# NE-CurrentSense-V1_0.net
KiCad netlist of a schematic drawn in Altium Designer
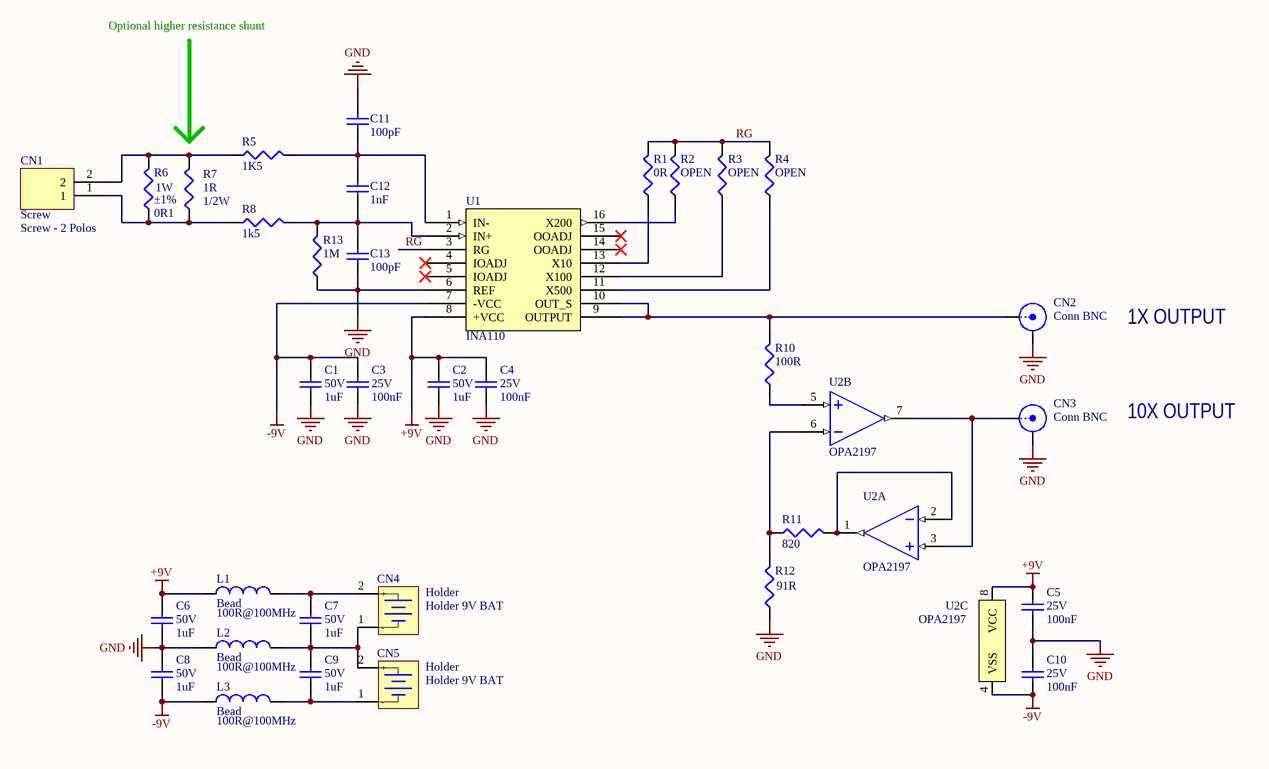
[diagram p0: NE-CurrentSense-V1.0.SchDoc]

(export (version "E")
  (design (tool "Eeschema 10.0.6"))
  (components
    (comp (ref "C1")
      (value "1uF")
      (footprint "CC0603")
      (description "Capacitor (Semiconductor SIM Model)")
      (fields (field (name "TENSÃO") "50V") (field (name "Comment") "Capacitor Cerâmico"))
      (libsource (lib "NavarroCAP") (part "Cap 1uF 50V 0603 X5R"))
    )
    (comp (ref "C2")
      (value "1uF")
      (footprint "CC0603")
      (description "Capacitor (Semiconductor SIM Model)")
      (fields (field (name "TENSÃO") "50V") (field (name "Comment") "Capacitor Cerâmico"))
      (libsource (lib "NavarroCAP") (part "Cap 1uF 50V 0603 X5R"))
    )
    (comp (ref "C3")
      (value "100nF")
      (footprint "CC0603")
      (description "Capacitor (Semiconductor SIM Model)")
      (fields (field (name "TENSÃO") "25V") (field (name "Comment") "Capacitor Cerâmico"))
      (libsource (lib "NavarroCAP") (part "Cap 100nF 25V 0603 X7R"))
    )
    (comp (ref "C4")
      (value "100nF")
      (footprint "CC0603")
      (description "Capacitor (Semiconductor SIM Model)")
      (fields (field (name "TENSÃO") "25V") (field (name "Comment") "Capacitor Cerâmico"))
      (libsource (lib "NavarroCAP") (part "Cap 100nF 25V 0603 X7R"))
    )
    (comp (ref "C5")
      (value "100nF")
      (footprint "CC0603")
      (description "Capacitor (Semiconductor SIM Model)")
      (fields (field (name "TENSÃO") "25V") (field (name "Comment") "Capacitor Cerâmico"))
      (libsource (lib "NavarroCAP") (part "Cap 100nF 25V 0603 X7R"))
    )
    (comp (ref "C6")
      (value "1uF")
      (footprint "CC0603")
      (description "Capacitor (Semiconductor SIM Model)")
      (fields (field (name "TENSÃO") "50V") (field (name "Comment") "Capacitor Cerâmico"))
      (libsource (lib "NavarroCAP") (part "Cap 1uF 50V 0603 X5R"))
    )
    (comp (ref "C7")
      (value "1uF")
      (footprint "CC0603")
      (description "Capacitor (Semiconductor SIM Model)")
      (fields (field (name "TENSÃO") "50V") (field (name "Comment") "Capacitor Cerâmico"))
      (libsource (lib "NavarroCAP") (part "Cap 1uF 50V 0603 X5R"))
    )
    (comp (ref "C8")
      (value "1uF")
      (footprint "CC0603")
      (description "Capacitor (Semiconductor SIM Model)")
      (fields (field (name "TENSÃO") "50V") (field (name "Comment") "Capacitor Cerâmico"))
      (libsource (lib "NavarroCAP") (part "Cap 1uF 50V 0603 X5R"))
    )
    (comp (ref "C9")
      (value "1uF")
      (footprint "CC0603")
      (description "Capacitor (Semiconductor SIM Model)")
      (fields (field (name "TENSÃO") "50V") (field (name "Comment") "Capacitor Cerâmico"))
      (libsource (lib "NavarroCAP") (part "Cap 1uF 50V 0603 X5R"))
    )
    (comp (ref "C10")
      (value "100nF")
      (footprint "CC0603")
      (description "Capacitor (Semiconductor SIM Model)")
      (fields (field (name "TENSÃO") "25V") (field (name "Comment") "Capacitor Cerâmico"))
      (libsource (lib "NavarroCAP") (part "Cap 100nF 25V 0603 X7R"))
    )
    (comp (ref "C11")
      (value "100pF")
      (footprint "CC0603")
      (description "Capacitor (Semiconductor SIM Model)")
      (fields (field (name "Comment") "Capacitor Cerâmico"))
      (libsource (lib "NavarroCAP") (part "Cap OPEN 0603"))
    )
    (comp (ref "C12")
      (value "1nF")
      (footprint "CC0603")
      (description "Capacitor (Semiconductor SIM Model)")
      (fields (field (name "Comment") "Capacitor Cerâmico"))
      (libsource (lib "NavarroCAP") (part "Cap OPEN 0603"))
    )
    (comp (ref "C13")
      (value "100pF")
      (footprint "CC0603")
      (description "Capacitor (Semiconductor SIM Model)")
      (fields (field (name "Comment") "Capacitor Cerâmico"))
      (libsource (lib "NavarroCAP") (part "Cap OPEN 0603"))
    )
    (comp (ref "CN1")
      (value "Screw")
      (footprint "CONN SCREW-2N P5.08")
      (description "Conector Screw Block")
      (fields (field (name "ALTIUM_VALUE") "Screw - 2 Polos"))
      (libsource (lib "TecnocladeCON") (part "Screw-2 300V 12A P5.08mm"))
    )
    (comp (ref "CN2")
      (value "Conn BNC")
      (footprint "CONN BNC-JACK")
      (description "Conector BNC")
      (libsource (lib "TecnocladeCON") (part "Conn BNC"))
    )
    (comp (ref "CN3")
      (value "Conn BNC")
      (footprint "CONN BNC-JACK")
      (description "Conector BNC")
      (libsource (lib "TecnocladeCON") (part "Conn BNC"))
    )
    (comp (ref "CN4")
      (value "Holder")
      (footprint "BATTHOLDER-9V-BH9V-PC-ND")
      (fields (field (name "ALTIUM_VALUE") "Holder 9V BAT"))
      (libsource (lib "NavarroCON") (part "BattHolder 9V"))
    )
    (comp (ref "CN5")
      (value "Holder")
      (footprint "BATTHOLDER-9V-BH9V-PC-ND")
      (fields (field (name "ALTIUM_VALUE") "Holder 9V BAT"))
      (libsource (lib "NavarroCON") (part "BattHolder 9V"))
    )
    (comp (ref "L1")
      (value "Bead")
      (footprint "CC0603")
      (fields (field (name "ALTIUM_VALUE") "100R@100MHz"))
      (libsource (lib "NavarroIND") (part "Bd 100R@100MHz 0603 2A"))
    )
    (comp (ref "L2")
      (value "Bead")
      (footprint "CC0603")
      (fields (field (name "ALTIUM_VALUE") "100R@100MHz"))
      (libsource (lib "NavarroIND") (part "Bd 100R@100MHz 0603 2A"))
    )
    (comp (ref "L3")
      (value "Bead")
      (footprint "CC0603")
      (fields (field (name "ALTIUM_VALUE") "100R@100MHz"))
      (libsource (lib "NavarroIND") (part "Bd 100R@100MHz 0603 2A"))
    )
    (comp (ref "R1")
      (value "0R")
      (footprint "CC0603")
      (description "Resistor")
      (libsource (lib "NavarroRES") (part "Res 0R 0603 1/10W"))
    )
    (comp (ref "R2")
      (value "OPEN")
      (footprint "CC0603")
      (description "Resistor")
      (fields (field (name "Comment") "Resistor Open"))
      (libsource (lib "NavarroRES") (part "Res Open 0603"))
    )
    (comp (ref "R3")
      (value "OPEN")
      (footprint "CC0603")
      (description "Resistor")
      (fields (field (name "Comment") "Resistor Open"))
      (libsource (lib "NavarroRES") (part "Res Open 0603"))
    )
    (comp (ref "R4")
      (value "OPEN")
      (footprint "CC0603")
      (description "Resistor")
      (fields (field (name "Comment") "Resistor Open"))
      (libsource (lib "NavarroRES") (part "Res Open 0603"))
    )
    (comp (ref "R5")
      (value "1K5")
      (footprint "CC0603")
      (description "Resistor")
      (libsource (lib "NavarroRES") (part "Res 0R 0603 1/10W"))
    )
    (comp (ref "R6")
      (value "0R1")
      (footprint "CC2010")
      (description "Resistor Shunt")
      (fields
        (field (name "POTÊNCIA") "1W")
        (field (name "TOLERÂNCIA") "±1%")
        (field (name "Comment") "Resistor")
      )
      (libsource (lib "NavarroRES") (part "Shunt 0R1 1% 2010 1W"))
    )
    (comp (ref "R7")
      (value "1R")
      (footprint "CC1206")
      (description "Resistor")
      (fields (field (name "POTÊNCIA") "1/2W"))
      (libsource (lib "NavarroRES") (part "Res 931R 1% 0603 1/10W"))
    )
    (comp (ref "R8")
      (value "1k5")
      (footprint "CC0603")
      (description "Resistor")
      (libsource (lib "NavarroRES") (part "Res 0R 0603 1/10W"))
    )
    (comp (ref "R10")
      (value "100R")
      (footprint "CC0603")
      (description "Resistor")
      (libsource (lib "NavarroRES") (part "Res 100R 5% 0603 1/10W"))
    )
    (comp (ref "R11")
      (value "820")
      (footprint "CC0603")
      (description "Resistor")
      (libsource (lib "NavarroRES") (part "Res 9K76 1% 0603 1/10W"))
    )
    (comp (ref "R12")
      (value "91R")
      (footprint "CC0603")
      (description "Resistor")
      (libsource (lib "NavarroRES") (part "Res 976R 1% 0603 1/10W"))
    )
    (comp (ref "R13")
      (value "1M")
      (footprint "CC0603")
      (description "Resistor")
      (libsource (lib "NavarroRES") (part "Res 1M 1% 0603 1/10W"))
    )
    (comp (ref "U1")
      (value "INA110")
      (footprint "SOIC-16N_WIDE")
      (description "Fast-Settling FET-Input  INSTRUMENTATION AMPLIFIER")
      (libsource (lib "Navarro") (part "INA110"))
    )
    (comp (ref "U2")
      (value "OPA2197")
      (footprint "SOIC-8N")
      (description "OPAx197 36-V, Precision, Rail-to-Rail Input/Output, Low Offset Voltage, Operational Amplifiers")
      (libsource (lib "Navarro") (part "OPA2197"))
    )
  )
  (nets
    (net (code "1") (name "+9V") (class "Default")
      (node (ref "C2") (pin "2") (pinfunction "2_2") (pintype "passive"))
      (node (ref "C4") (pin "2") (pinfunction "2_2") (pintype "passive"))
      (node (ref "C5") (pin "2") (pinfunction "2_2") (pintype "passive"))
      (node (ref "C6") (pin "2") (pinfunction "2_2") (pintype "passive"))
      (node (ref "L1") (pin "1") (pinfunction "1_1") (pintype "passive"))
      (node (ref "U1") (pin "8") (pinfunction "+VCC_8") (pintype "power_in"))
      (node (ref "U2") (pin "8") (pinfunction "VCC_8") (pintype "power_in"))
    )
    (net (code "2") (name "-9V") (class "Default")
      (node (ref "C1") (pin "2") (pinfunction "2_2") (pintype "passive"))
      (node (ref "C10") (pin "1") (pinfunction "1_1") (pintype "passive"))
      (node (ref "C3") (pin "2") (pinfunction "2_2") (pintype "passive"))
      (node (ref "C8") (pin "1") (pinfunction "1_1") (pintype "passive"))
      (node (ref "L3") (pin "1") (pinfunction "1_1") (pintype "passive"))
      (node (ref "U1") (pin "7") (pinfunction "-VCC_7") (pintype "power_in"))
      (node (ref "U2") (pin "4") (pinfunction "VSS_4") (pintype "power_in"))
    )
    (net (code "3") (name "/RG") (class "Default")
      (node (ref "R1") (pin "2") (pinfunction "2_2") (pintype "passive"))
      (node (ref "R2") (pin "2") (pinfunction "2_2") (pintype "passive"))
      (node (ref "R3") (pin "2") (pinfunction "2_2") (pintype "passive"))
      (node (ref "R4") (pin "2") (pinfunction "2_2") (pintype "passive"))
      (node (ref "U1") (pin "3") (pinfunction "RG_3") (pintype "passive"))
    )
    (net (code "4") (name "GND") (class "Default")
      (node (ref "C1") (pin "1") (pinfunction "1_1") (pintype "passive"))
      (node (ref "C10") (pin "2") (pinfunction "2_2") (pintype "passive"))
      (node (ref "C11") (pin "2") (pinfunction "2_2") (pintype "passive"))
      (node (ref "C13") (pin "1") (pinfunction "1_1") (pintype "passive"))
      (node (ref "C2") (pin "1") (pinfunction "1_1") (pintype "passive"))
      (node (ref "C3") (pin "1") (pinfunction "1_1") (pintype "passive"))
      (node (ref "C4") (pin "1") (pinfunction "1_1") (pintype "passive"))
      (node (ref "C5") (pin "1") (pinfunction "1_1") (pintype "passive"))
      (node (ref "C6") (pin "1") (pinfunction "1_1") (pintype "passive"))
      (node (ref "C8") (pin "2") (pinfunction "2_2") (pintype "passive"))
      (node (ref "CN2") (pin "2") (pinfunction "Y_2") (pintype "passive"))
      (node (ref "CN3") (pin "2") (pinfunction "Y_2") (pintype "passive"))
      (node (ref "L2") (pin "1") (pinfunction "1_1") (pintype "passive"))
      (node (ref "R12") (pin "1") (pinfunction "1_1") (pintype "passive"))
      (node (ref "R13") (pin "1") (pinfunction "1_1") (pintype "passive"))
      (node (ref "U1") (pin "6") (pinfunction "REF_6") (pintype "passive"))
    )
    (net (code "5") (name "Net-(CN1-Pad1)") (class "Default")
      (node (ref "CN1") (pin "1") (pinfunction "1_1") (pintype "passive"))
      (node (ref "R6") (pin "1") (pinfunction "1_1") (pintype "passive"))
      (node (ref "R7") (pin "1") (pinfunction "1_1") (pintype "passive"))
      (node (ref "R8") (pin "1") (pinfunction "1_1") (pintype "passive"))
    )
    (net (code "6") (name "Net-(CN1-Pad2)") (class "Default")
      (node (ref "CN1") (pin "2") (pinfunction "2_2") (pintype "passive"))
      (node (ref "R5") (pin "1") (pinfunction "1_1") (pintype "passive"))
      (node (ref "R6") (pin "2") (pinfunction "2_2") (pintype "passive"))
      (node (ref "R7") (pin "2") (pinfunction "2_2") (pintype "passive"))
    )
    (net (code "7") (name "Net-(CN2-X)") (class "Default")
      (node (ref "CN2") (pin "1") (pinfunction "X_1") (pintype "passive"))
      (node (ref "R10") (pin "2") (pinfunction "2_2") (pintype "passive"))
      (node (ref "U1") (pin "10") (pinfunction "OUT_S_10") (pintype "passive"))
      (node (ref "U1") (pin "9") (pinfunction "OUTPUT_9") (pintype "passive"))
    )
    (net (code "8") (name "Net-(CN3-X)") (class "Default")
      (node (ref "CN3") (pin "1") (pinfunction "X_1") (pintype "passive"))
      (node (ref "U2") (pin "3") (pinfunction "INA+_3") (pintype "input"))
      (node (ref "U2") (pin "7") (pinfunction "OUTB_7") (pintype "output"))
    )
    (net (code "9") (name "Net-(CN4-+)") (class "Default")
      (node (ref "C7") (pin "2") (pinfunction "2_2") (pintype "passive"))
      (node (ref "CN4") (pin "2") (pinfunction "+_2") (pintype "power_in"))
      (node (ref "L1") (pin "2") (pinfunction "2_2") (pintype "passive"))
    )
    (net (code "10") (name "Net-(CN4--)") (class "Default")
      (node (ref "C7") (pin "1") (pinfunction "1_1") (pintype "passive"))
      (node (ref "C9") (pin "2") (pinfunction "2_2") (pintype "passive"))
      (node (ref "CN4") (pin "1") (pinfunction "-_1") (pintype "power_in"))
      (node (ref "CN5") (pin "2") (pinfunction "+_2") (pintype "power_in"))
      (node (ref "L2") (pin "2") (pinfunction "2_2") (pintype "passive"))
    )
    (net (code "11") (name "Net-(CN5--)") (class "Default")
      (node (ref "C9") (pin "1") (pinfunction "1_1") (pintype "passive"))
      (node (ref "CN5") (pin "1") (pinfunction "-_1") (pintype "power_in"))
      (node (ref "L3") (pin "2") (pinfunction "2_2") (pintype "passive"))
    )
    (net (code "12") (name "Net-(U1-IN+)") (class "Default")
      (node (ref "C12") (pin "1") (pinfunction "1_1") (pintype "passive"))
      (node (ref "C13") (pin "2") (pinfunction "2_2") (pintype "passive"))
      (node (ref "R13") (pin "2") (pinfunction "2_2") (pintype "passive"))
      (node (ref "R8") (pin "2") (pinfunction "2_2") (pintype "passive"))
      (node (ref "U1") (pin "2") (pinfunction "IN+_2") (pintype "input"))
    )
    (net (code "13") (name "Net-(U1-IN-)") (class "Default")
      (node (ref "C11") (pin "1") (pinfunction "1_1") (pintype "passive"))
      (node (ref "C12") (pin "2") (pinfunction "2_2") (pintype "passive"))
      (node (ref "R5") (pin "2") (pinfunction "2_2") (pintype "passive"))
      (node (ref "U1") (pin "1") (pinfunction "IN-_1") (pintype "input"))
    )
    (net (code "14") (name "Net-(U1-X10)") (class "Default")
      (node (ref "R1") (pin "1") (pinfunction "1_1") (pintype "passive"))
      (node (ref "U1") (pin "13") (pinfunction "X10_13") (pintype "passive"))
    )
    (net (code "15") (name "Net-(U1-X100)") (class "Default")
      (node (ref "R3") (pin "1") (pinfunction "1_1") (pintype "passive"))
      (node (ref "U1") (pin "12") (pinfunction "X100_12") (pintype "passive"))
    )
    (net (code "16") (name "Net-(U1-X200)") (class "Default")
      (node (ref "R2") (pin "1") (pinfunction "1_1") (pintype "passive"))
      (node (ref "U1") (pin "16") (pinfunction "X200_16") (pintype "output"))
    )
    (net (code "17") (name "Net-(U1-X500)") (class "Default")
      (node (ref "R4") (pin "1") (pinfunction "1_1") (pintype "passive"))
      (node (ref "U1") (pin "11") (pinfunction "X500_11") (pintype "passive"))
    )
    (net (code "18") (name "Net-(U2A-INA-)") (class "Default")
      (node (ref "R11") (pin "2") (pinfunction "2_2") (pintype "passive"))
      (node (ref "U2") (pin "1") (pinfunction "OUTA_1") (pintype "output"))
      (node (ref "U2") (pin "2") (pinfunction "INA-_2") (pintype "input"))
    )
    (net (code "19") (name "Net-(U2B-INB+)") (class "Default")
      (node (ref "R10") (pin "1") (pinfunction "1_1") (pintype "passive"))
      (node (ref "U2") (pin "5") (pinfunction "INB+_5") (pintype "input"))
    )
    (net (code "20") (name "Net-(U2B-INB-)") (class "Default")
      (node (ref "R11") (pin "1") (pinfunction "1_1") (pintype "passive"))
      (node (ref "R12") (pin "2") (pinfunction "2_2") (pintype "passive"))
      (node (ref "U2") (pin "6") (pinfunction "INB-_6") (pintype "input"))
    )
    (net (code "21") (name "unconnected-(U1-IOADJ-Pad4)") (class "Default")
      (node (ref "U1") (pin "4") (pinfunction "IOADJ_4") (pintype "passive+no_connect"))
    )
    (net (code "22") (name "unconnected-(U1-IOADJ-Pad5)") (class "Default")
      (node (ref "U1") (pin "5") (pinfunction "IOADJ_5") (pintype "passive+no_connect"))
    )
    (net (code "23") (name "unconnected-(U1-OOADJ-Pad14)") (class "Default")
      (node (ref "U1") (pin "14") (pinfunction "OOADJ_14") (pintype "passive+no_connect"))
    )
    (net (code "24") (name "unconnected-(U1-OOADJ-Pad15)") (class "Default")
      (node (ref "U1") (pin "15") (pinfunction "OOADJ_15") (pintype "passive+no_connect"))
    )
  )
)
